# SCH_Pico_to_Rpi4_2023-11-27.net
KiCad netlist of a schematic drawn in EasyEDA
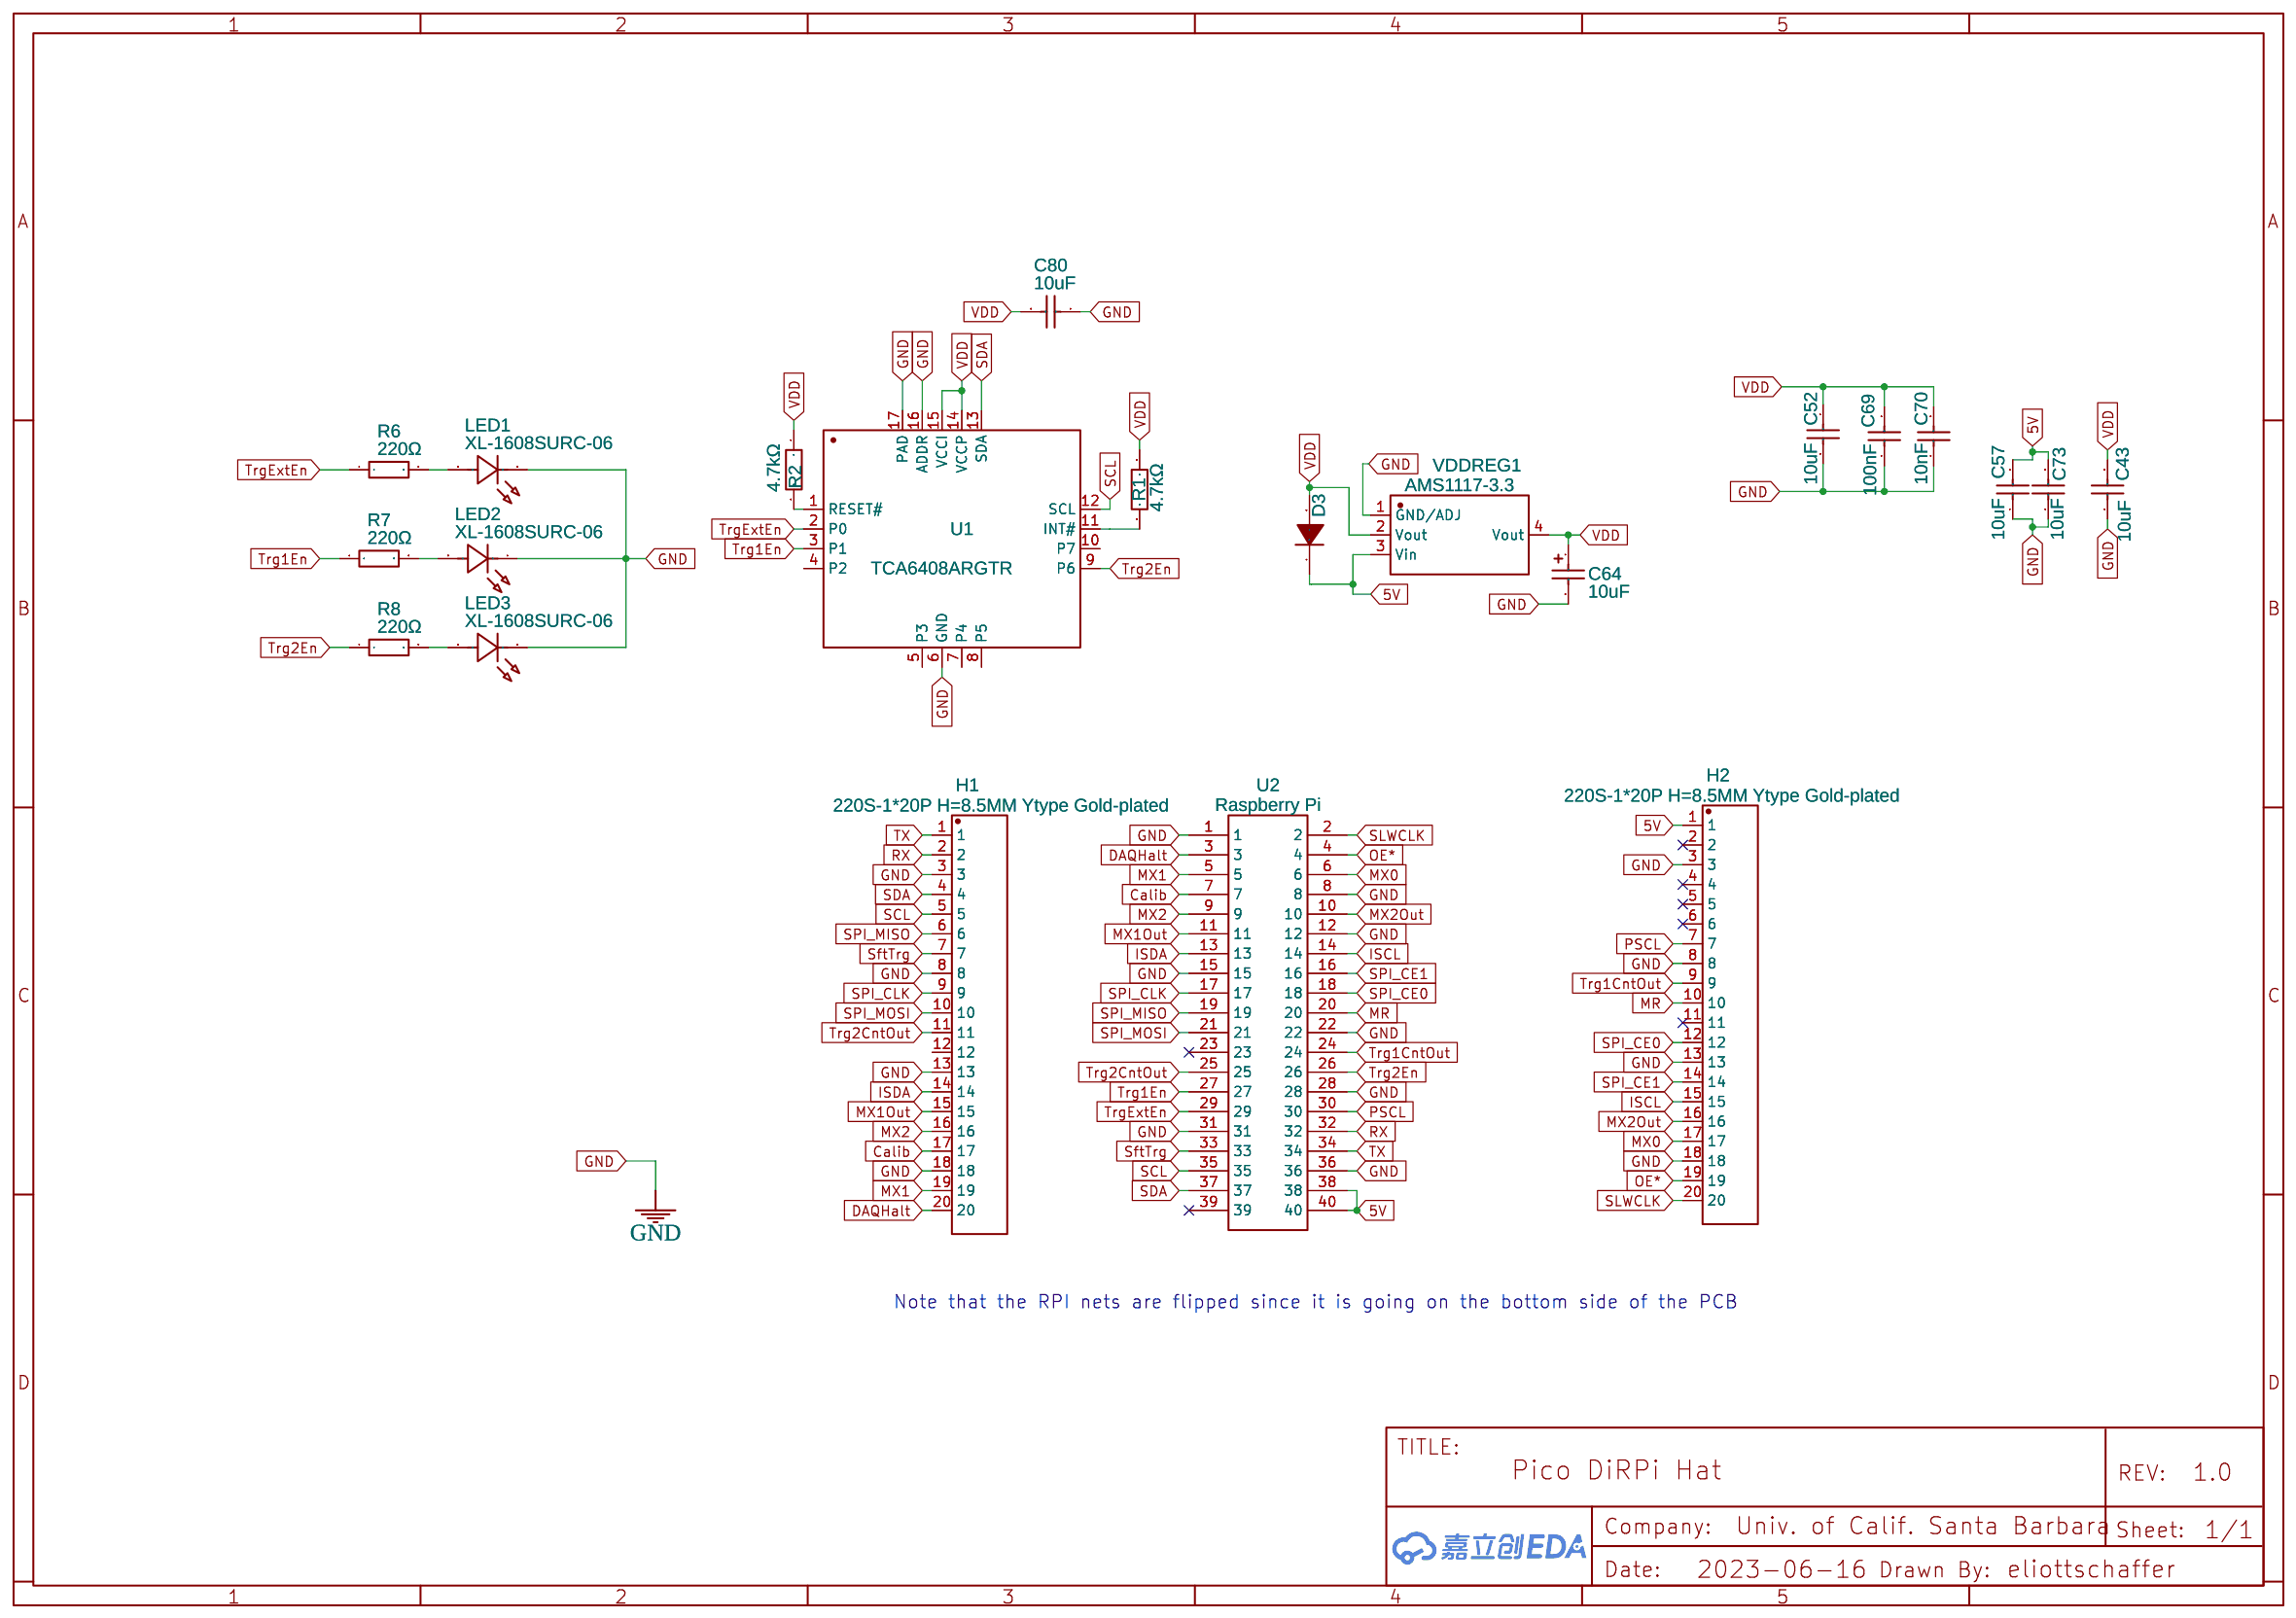
[diagram p0: schematic sheet]

(export (version "E")
  (design (tool "Eeschema 10.0.6"))
  (components
    (comp (ref "C43")
      (value "10uF")
      (fields (field (name "Manufacturer Part") "CL05A106MQ5NUNC") (field (name "Manufacturer") "SAMSUNG"))
      (libsource (lib "") (part "CL05A106MQ5NUNC"))
    )
    (comp (ref "C52")
      (value "10uF")
      (fields (field (name "Manufacturer Part") "CL05A106MQ5NUNC") (field (name "Manufacturer") "SAMSUNG"))
      (libsource (lib "") (part "CL05A106MQ5NUNC_1"))
    )
    (comp (ref "C57")
      (value "10uF")
      (fields (field (name "Manufacturer Part") "CL05A106MQ5NUNC") (field (name "Manufacturer") "SAMSUNG"))
      (libsource (lib "") (part "CL05A106MQ5NUNC"))
    )
    (comp (ref "C64")
      (value "10uF")
      (fields (field (name "Manufacturer Part") "TAJA106K016RNJ") (field (name "Manufacturer") "AVX"))
      (libsource (lib "") (part "TAJA106K016RNJ"))
    )
    (comp (ref "C69")
      (value "100nF")
      (fields (field (name "Manufacturer Part") "CL05B104KO5NNNC") (field (name "Manufacturer") "SAMSUNG"))
      (libsource (lib "") (part "CL05B104KO5NNNC"))
    )
    (comp (ref "C70")
      (value "10nF")
      (fields (field (name "Manufacturer Part") "CL05B103KB5NNNC") (field (name "Manufacturer") "SAMSUNG"))
      (libsource (lib "") (part "CL05B103KB5NNNC"))
    )
    (comp (ref "C73")
      (value "10uF")
      (fields (field (name "Manufacturer Part") "CL05A106MQ5NUNC") (field (name "Manufacturer") "SAMSUNG"))
      (libsource (lib "") (part "CL05A106MQ5NUNC"))
    )
    (comp (ref "C80")
      (value "10uF")
      (fields (field (name "Manufacturer Part") "CL05A106MQ5NUNC") (field (name "Manufacturer") "SAMSUNG"))
      (libsource (lib "") (part "CL05A106MQ5NUNC_2"))
    )
    (comp (ref "D3")
      (value "M7_C95872")
      (fields (field (name "Manufacturer Part") "M7") (field (name "Manufacturer") "MDD"))
      (libsource (lib "") (part "M7_C95872"))
    )
    (comp (ref "H1")
      (value "220S-1*20P H=8.5MM Ytype Gold-plated")
      (fields (field (name "Manufacturer Part") "B-2200S20P-A120") (field (name "Manufacturer") "Ckmtw(灿科盟)"))
      (libsource (lib "") (part "220S-1*20P H=8.5MM Ytype Gold-plated"))
    )
    (comp (ref "H2")
      (value "220S-1*20P H=8.5MM Ytype Gold-plated")
      (fields (field (name "Manufacturer Part") "B-2200S20P-A120") (field (name "Manufacturer") "Ckmtw(灿科盟)"))
      (libsource (lib "") (part "220S-1*20P H=8.5MM Ytype Gold-plated"))
    )
    (comp (ref "LED1")
      (value "XL-1608SURC-06")
      (fields (field (name "Manufacturer") "XINGLIGHT(成兴光)"))
      (libsource (lib "") (part "XL-1608SURC-06"))
    )
    (comp (ref "LED2")
      (value "XL-1608SURC-06")
      (fields (field (name "Manufacturer") "XINGLIGHT(成兴光)"))
      (libsource (lib "") (part "XL-1608SURC-06"))
    )
    (comp (ref "LED3")
      (value "XL-1608SURC-06")
      (fields (field (name "Manufacturer") "XINGLIGHT(成兴光)"))
      (libsource (lib "") (part "XL-1608SURC-06"))
    )
    (comp (ref "R1")
      (value "4.7kΩ")
      (fields (field (name "Manufacturer Part") "0402WGF4701TCE") (field (name "Manufacturer") "UniOhm"))
      (libsource (lib "") (part "0402WGF4701TCE"))
    )
    (comp (ref "R2")
      (value "4.7kΩ")
      (fields (field (name "Manufacturer Part") "0402WGF4701TCE") (field (name "Manufacturer") "UniOhm"))
      (libsource (lib "") (part "0402WGF4701TCE"))
    )
    (comp (ref "R6")
      (value "220Ω")
      (fields (field (name "Manufacturer Part") "AC0805FR-07220RL") (field (name "Manufacturer") "YAGEO(国巨)"))
      (libsource (lib "") (part "AC0805FR-07220RL"))
    )
    (comp (ref "R7")
      (value "220Ω")
      (fields (field (name "Manufacturer Part") "AC0805FR-07220RL") (field (name "Manufacturer") "YAGEO(国巨)"))
      (libsource (lib "") (part "AC0805FR-07220RL"))
    )
    (comp (ref "R8")
      (value "220Ω")
      (fields (field (name "Manufacturer Part") "AC0805FR-07220RL") (field (name "Manufacturer") "YAGEO(国巨)"))
      (libsource (lib "") (part "AC0805FR-07220RL"))
    )
    (comp (ref "U1")
      (value "TCA6408ARGTR")
      (fields (field (name "Manufacturer") "TI(德州仪器)"))
      (libsource (lib "") (part "TCA6408ARGTR"))
    )
    (comp (ref "U2")
      (value "Raspberry Pi")
      (fields (field (name "Manufacturer Part") "2.54-2*20") (field (name "Manufacturer") "ZHOURI(洲日)"))
      (libsource (lib "") (part "2.54-2*20"))
    )
    (comp (ref "VDDREG1")
      (value "AMS1117-3.3")
      (fields (field (name "Manufacturer") "AMS"))
      (libsource (lib "") (part "AMS1117-3.3"))
    )
  )
  (nets
    (net (code "1") (name "5V") (class "Default")
      (node (ref "C57") (pin "2") (pinfunction "2_2") (pintype "input"))
      (node (ref "C73") (pin "2") (pinfunction "2_2") (pintype "input"))
      (node (ref "D3") (pin "1") (pinfunction "K_1") (pintype "unspecified"))
      (node (ref "H2") (pin "1") (pinfunction "1_1") (pintype "unspecified"))
      (node (ref "U2") (pin "38") (pinfunction "38_38") (pintype "unspecified"))
      (node (ref "U2") (pin "40") (pinfunction "40_40") (pintype "unspecified"))
      (node (ref "VDDREG1") (pin "3") (pinfunction "Vin_3") (pintype "unspecified"))
    )
    (net (code "2") (name "Calib") (class "Default")
      (node (ref "H1") (pin "17") (pinfunction "17_17") (pintype "unspecified"))
      (node (ref "U2") (pin "7") (pinfunction "7_7") (pintype "unspecified"))
    )
    (net (code "3") (name "DAQHalt") (class "Default")
      (node (ref "H1") (pin "20") (pinfunction "20_20") (pintype "unspecified"))
      (node (ref "U2") (pin "3") (pinfunction "3_3") (pintype "unspecified"))
    )
    (net (code "4") (name "GND") (class "Default")
      (node (ref "C43") (pin "1") (pinfunction "1_1") (pintype "input"))
      (node (ref "C52") (pin "2") (pinfunction "2_2") (pintype "input"))
      (node (ref "C57") (pin "1") (pinfunction "1_1") (pintype "input"))
      (node (ref "C64") (pin "2") (pinfunction "2_2") (pintype "input"))
      (node (ref "C69") (pin "1") (pinfunction "1_1") (pintype "input"))
      (node (ref "C70") (pin "1") (pinfunction "1_1") (pintype "input"))
      (node (ref "C73") (pin "1") (pinfunction "1_1") (pintype "input"))
      (node (ref "C80") (pin "1") (pinfunction "1_1") (pintype "input"))
      (node (ref "H1") (pin "13") (pinfunction "13_13") (pintype "unspecified"))
      (node (ref "H1") (pin "18") (pinfunction "18_18") (pintype "unspecified"))
      (node (ref "H1") (pin "3") (pinfunction "3_3") (pintype "unspecified"))
      (node (ref "H1") (pin "8") (pinfunction "8_8") (pintype "unspecified"))
      (node (ref "H2") (pin "13") (pinfunction "13_13") (pintype "unspecified"))
      (node (ref "H2") (pin "18") (pinfunction "18_18") (pintype "unspecified"))
      (node (ref "H2") (pin "3") (pinfunction "3_3") (pintype "unspecified"))
      (node (ref "H2") (pin "8") (pinfunction "8_8") (pintype "unspecified"))
      (node (ref "LED1") (pin "1") (pinfunction "K_1") (pintype "unspecified"))
      (node (ref "LED2") (pin "1") (pinfunction "K_1") (pintype "unspecified"))
      (node (ref "LED3") (pin "1") (pinfunction "K_1") (pintype "unspecified"))
      (node (ref "U1") (pin "16") (pinfunction "ADDR_16") (pintype "unspecified"))
      (node (ref "U1") (pin "17") (pinfunction "PAD_17") (pintype "unspecified"))
      (node (ref "U1") (pin "6") (pinfunction "GND_6") (pintype "unspecified"))
      (node (ref "U2") (pin "1") (pinfunction "1_1") (pintype "unspecified"))
      (node (ref "U2") (pin "12") (pinfunction "12_12") (pintype "unspecified"))
      (node (ref "U2") (pin "15") (pinfunction "15_15") (pintype "unspecified"))
      (node (ref "U2") (pin "22") (pinfunction "22_22") (pintype "unspecified"))
      (node (ref "U2") (pin "28") (pinfunction "28_28") (pintype "unspecified"))
      (node (ref "U2") (pin "31") (pinfunction "31_31") (pintype "unspecified"))
      (node (ref "U2") (pin "36") (pinfunction "36_36") (pintype "unspecified"))
      (node (ref "U2") (pin "8") (pinfunction "8_8") (pintype "unspecified"))
      (node (ref "VDDREG1") (pin "1") (pinfunction "GND/ADJ_1") (pintype "unspecified"))
    )
    (net (code "5") (name "ISCL") (class "Default")
      (node (ref "H2") (pin "15") (pinfunction "15_15") (pintype "unspecified"))
      (node (ref "U2") (pin "14") (pinfunction "14_14") (pintype "unspecified"))
    )
    (net (code "6") (name "ISDA") (class "Default")
      (node (ref "H1") (pin "14") (pinfunction "14_14") (pintype "unspecified"))
      (node (ref "U2") (pin "13") (pinfunction "13_13") (pintype "unspecified"))
    )
    (net (code "7") (name "MR") (class "Default")
      (node (ref "H2") (pin "10") (pinfunction "10_10") (pintype "unspecified"))
      (node (ref "U2") (pin "20") (pinfunction "20_20") (pintype "unspecified"))
    )
    (net (code "8") (name "MX0") (class "Default")
      (node (ref "H2") (pin "17") (pinfunction "17_17") (pintype "unspecified"))
      (node (ref "U2") (pin "6") (pinfunction "6_6") (pintype "unspecified"))
    )
    (net (code "9") (name "MX1") (class "Default")
      (node (ref "H1") (pin "19") (pinfunction "19_19") (pintype "unspecified"))
      (node (ref "U2") (pin "5") (pinfunction "5_5") (pintype "unspecified"))
    )
    (net (code "10") (name "MX1Out") (class "Default")
      (node (ref "H1") (pin "15") (pinfunction "15_15") (pintype "unspecified"))
      (node (ref "U2") (pin "11") (pinfunction "11_11") (pintype "unspecified"))
    )
    (net (code "11") (name "MX2") (class "Default")
      (node (ref "H1") (pin "16") (pinfunction "16_16") (pintype "unspecified"))
      (node (ref "U2") (pin "9") (pinfunction "9_9") (pintype "unspecified"))
    )
    (net (code "12") (name "MX2Out") (class "Default")
      (node (ref "H2") (pin "16") (pinfunction "16_16") (pintype "unspecified"))
      (node (ref "U2") (pin "10") (pinfunction "10_10") (pintype "unspecified"))
    )
    (net (code "13") (name "Net-(LED1-A)") (class "Default")
      (node (ref "LED1") (pin "2") (pinfunction "A_2") (pintype "unspecified"))
      (node (ref "R6") (pin "2") (pinfunction "2_2") (pintype "input"))
    )
    (net (code "14") (name "Net-(LED2-A)") (class "Default")
      (node (ref "LED2") (pin "2") (pinfunction "A_2") (pintype "unspecified"))
      (node (ref "R7") (pin "2") (pinfunction "2_2") (pintype "input"))
    )
    (net (code "15") (name "Net-(LED3-A)") (class "Default")
      (node (ref "LED3") (pin "2") (pinfunction "A_2") (pintype "unspecified"))
      (node (ref "R8") (pin "2") (pinfunction "2_2") (pintype "input"))
    )
    (net (code "16") (name "Net-(U1-INT#)") (class "Default")
      (node (ref "R1") (pin "2") (pinfunction "2_2") (pintype "input"))
      (node (ref "U1") (pin "11") (pinfunction "INT#_11") (pintype "unspecified"))
    )
    (net (code "17") (name "Net-(U1-RESET#)") (class "Default")
      (node (ref "R2") (pin "2") (pinfunction "2_2") (pintype "input"))
      (node (ref "U1") (pin "1") (pinfunction "RESET#_1") (pintype "unspecified"))
    )
    (net (code "18") (name "OE*") (class "Default")
      (node (ref "H2") (pin "19") (pinfunction "19_19") (pintype "unspecified"))
      (node (ref "U2") (pin "4") (pinfunction "4_4") (pintype "unspecified"))
    )
    (net (code "19") (name "PSCL") (class "Default")
      (node (ref "H2") (pin "7") (pinfunction "7_7") (pintype "unspecified"))
      (node (ref "U2") (pin "30") (pinfunction "30_30") (pintype "unspecified"))
    )
    (net (code "20") (name "RX") (class "Default")
      (node (ref "H1") (pin "2") (pinfunction "2_2") (pintype "unspecified"))
      (node (ref "U2") (pin "32") (pinfunction "32_32") (pintype "unspecified"))
    )
    (net (code "21") (name "SCL") (class "Default")
      (node (ref "H1") (pin "5") (pinfunction "5_5") (pintype "unspecified"))
      (node (ref "U1") (pin "12") (pinfunction "SCL_12") (pintype "unspecified"))
      (node (ref "U2") (pin "35") (pinfunction "35_35") (pintype "unspecified"))
    )
    (net (code "22") (name "SDA") (class "Default")
      (node (ref "H1") (pin "4") (pinfunction "4_4") (pintype "unspecified"))
      (node (ref "U1") (pin "13") (pinfunction "SDA_13") (pintype "unspecified"))
      (node (ref "U2") (pin "37") (pinfunction "37_37") (pintype "unspecified"))
    )
    (net (code "23") (name "SLWCLK") (class "Default")
      (node (ref "H2") (pin "20") (pinfunction "20_20") (pintype "unspecified"))
      (node (ref "U2") (pin "2") (pinfunction "2_2") (pintype "unspecified"))
    )
    (net (code "24") (name "SPI_CE0") (class "Default")
      (node (ref "H2") (pin "12") (pinfunction "12_12") (pintype "unspecified"))
      (node (ref "U2") (pin "18") (pinfunction "18_18") (pintype "unspecified"))
    )
    (net (code "25") (name "SPI_CE1") (class "Default")
      (node (ref "H2") (pin "14") (pinfunction "14_14") (pintype "unspecified"))
      (node (ref "U2") (pin "16") (pinfunction "16_16") (pintype "unspecified"))
    )
    (net (code "26") (name "SPI_CLK") (class "Default")
      (node (ref "H1") (pin "9") (pinfunction "9_9") (pintype "unspecified"))
      (node (ref "U2") (pin "17") (pinfunction "17_17") (pintype "unspecified"))
    )
    (net (code "27") (name "SPI_MISO") (class "Default")
      (node (ref "H1") (pin "6") (pinfunction "6_6") (pintype "unspecified"))
      (node (ref "U2") (pin "19") (pinfunction "19_19") (pintype "unspecified"))
    )
    (net (code "28") (name "SPI_MOSI") (class "Default")
      (node (ref "H1") (pin "10") (pinfunction "10_10") (pintype "unspecified"))
      (node (ref "U2") (pin "21") (pinfunction "21_21") (pintype "unspecified"))
    )
    (net (code "29") (name "SftTrg") (class "Default")
      (node (ref "H1") (pin "7") (pinfunction "7_7") (pintype "unspecified"))
      (node (ref "U2") (pin "33") (pinfunction "33_33") (pintype "unspecified"))
    )
    (net (code "30") (name "TX") (class "Default")
      (node (ref "H1") (pin "1") (pinfunction "1_1") (pintype "unspecified"))
      (node (ref "U2") (pin "34") (pinfunction "34_34") (pintype "unspecified"))
    )
    (net (code "31") (name "Trg1CntOut") (class "Default")
      (node (ref "H2") (pin "9") (pinfunction "9_9") (pintype "unspecified"))
      (node (ref "U2") (pin "24") (pinfunction "24_24") (pintype "unspecified"))
    )
    (net (code "32") (name "Trg1En") (class "Default")
      (node (ref "R7") (pin "1") (pinfunction "1_1") (pintype "input"))
      (node (ref "U1") (pin "3") (pinfunction "P1_3") (pintype "unspecified"))
      (node (ref "U2") (pin "27") (pinfunction "27_27") (pintype "unspecified"))
    )
    (net (code "33") (name "Trg2CntOut") (class "Default")
      (node (ref "H1") (pin "11") (pinfunction "11_11") (pintype "unspecified"))
      (node (ref "U2") (pin "25") (pinfunction "25_25") (pintype "unspecified"))
    )
    (net (code "34") (name "Trg2En") (class "Default")
      (node (ref "R8") (pin "1") (pinfunction "1_1") (pintype "input"))
      (node (ref "U1") (pin "9") (pinfunction "P6_9") (pintype "unspecified"))
      (node (ref "U2") (pin "26") (pinfunction "26_26") (pintype "unspecified"))
    )
    (net (code "35") (name "TrgExtEn") (class "Default")
      (node (ref "R6") (pin "1") (pinfunction "1_1") (pintype "input"))
      (node (ref "U1") (pin "2") (pinfunction "P0_2") (pintype "unspecified"))
      (node (ref "U2") (pin "29") (pinfunction "29_29") (pintype "unspecified"))
    )
    (net (code "36") (name "VDD") (class "Default")
      (node (ref "C43") (pin "2") (pinfunction "2_2") (pintype "input"))
      (node (ref "C52") (pin "1") (pinfunction "1_1") (pintype "input"))
      (node (ref "C64") (pin "1") (pinfunction "1_1") (pintype "input"))
      (node (ref "C69") (pin "2") (pinfunction "2_2") (pintype "input"))
      (node (ref "C70") (pin "2") (pinfunction "2_2") (pintype "input"))
      (node (ref "C80") (pin "2") (pinfunction "2_2") (pintype "input"))
      (node (ref "D3") (pin "2") (pinfunction "A_2") (pintype "unspecified"))
      (node (ref "R1") (pin "1") (pinfunction "1_1") (pintype "input"))
      (node (ref "R2") (pin "1") (pinfunction "1_1") (pintype "input"))
      (node (ref "U1") (pin "14") (pinfunction "VCCP_14") (pintype "unspecified"))
      (node (ref "U1") (pin "15") (pinfunction "VCCI_15") (pintype "unspecified"))
      (node (ref "VDDREG1") (pin "2") (pinfunction "Vout_2") (pintype "unspecified"))
      (node (ref "VDDREG1") (pin "4") (pinfunction "Vout_4") (pintype "unspecified"))
    )
    (net (code "37") (name "unconnected-(H1-Pad12)") (class "Default")
      (node (ref "H1") (pin "12") (pinfunction "12_12") (pintype "unspecified"))
    )
    (net (code "38") (name "unconnected-(H2-Pad2)") (class "Default")
      (node (ref "H2") (pin "2") (pinfunction "2_2") (pintype "unspecified+no_connect"))
    )
    (net (code "39") (name "unconnected-(H2-Pad4)") (class "Default")
      (node (ref "H2") (pin "4") (pinfunction "4_4") (pintype "unspecified+no_connect"))
    )
    (net (code "40") (name "unconnected-(H2-Pad5)") (class "Default")
      (node (ref "H2") (pin "5") (pinfunction "5_5") (pintype "unspecified+no_connect"))
    )
    (net (code "41") (name "unconnected-(H2-Pad6)") (class "Default")
      (node (ref "H2") (pin "6") (pinfunction "6_6") (pintype "unspecified+no_connect"))
    )
    (net (code "42") (name "unconnected-(H2-Pad11)") (class "Default")
      (node (ref "H2") (pin "11") (pinfunction "11_11") (pintype "unspecified+no_connect"))
    )
    (net (code "43") (name "unconnected-(U1-P2-Pad4)") (class "Default")
      (node (ref "U1") (pin "4") (pinfunction "P2_4") (pintype "unspecified"))
    )
    (net (code "44") (name "unconnected-(U1-P3-Pad5)") (class "Default")
      (node (ref "U1") (pin "5") (pinfunction "P3_5") (pintype "unspecified"))
    )
    (net (code "45") (name "unconnected-(U1-P4-Pad7)") (class "Default")
      (node (ref "U1") (pin "7") (pinfunction "P4_7") (pintype "unspecified"))
    )
    (net (code "46") (name "unconnected-(U1-P5-Pad8)") (class "Default")
      (node (ref "U1") (pin "8") (pinfunction "P5_8") (pintype "unspecified"))
    )
    (net (code "47") (name "unconnected-(U1-P7-Pad10)") (class "Default")
      (node (ref "U1") (pin "10") (pinfunction "P7_10") (pintype "unspecified"))
    )
    (net (code "48") (name "unconnected-(U2-Pad23)") (class "Default")
      (node (ref "U2") (pin "23") (pinfunction "23_23") (pintype "unspecified+no_connect"))
    )
    (net (code "49") (name "unconnected-(U2-Pad39)") (class "Default")
      (node (ref "U2") (pin "39") (pinfunction "39_39") (pintype "unspecified+no_connect"))
    )
  )
)
